# SCH_DTNEA-PRESS-MONITOR-RECIEVER_2021-12.net
KiCad netlist of a schematic drawn in EasyEDA
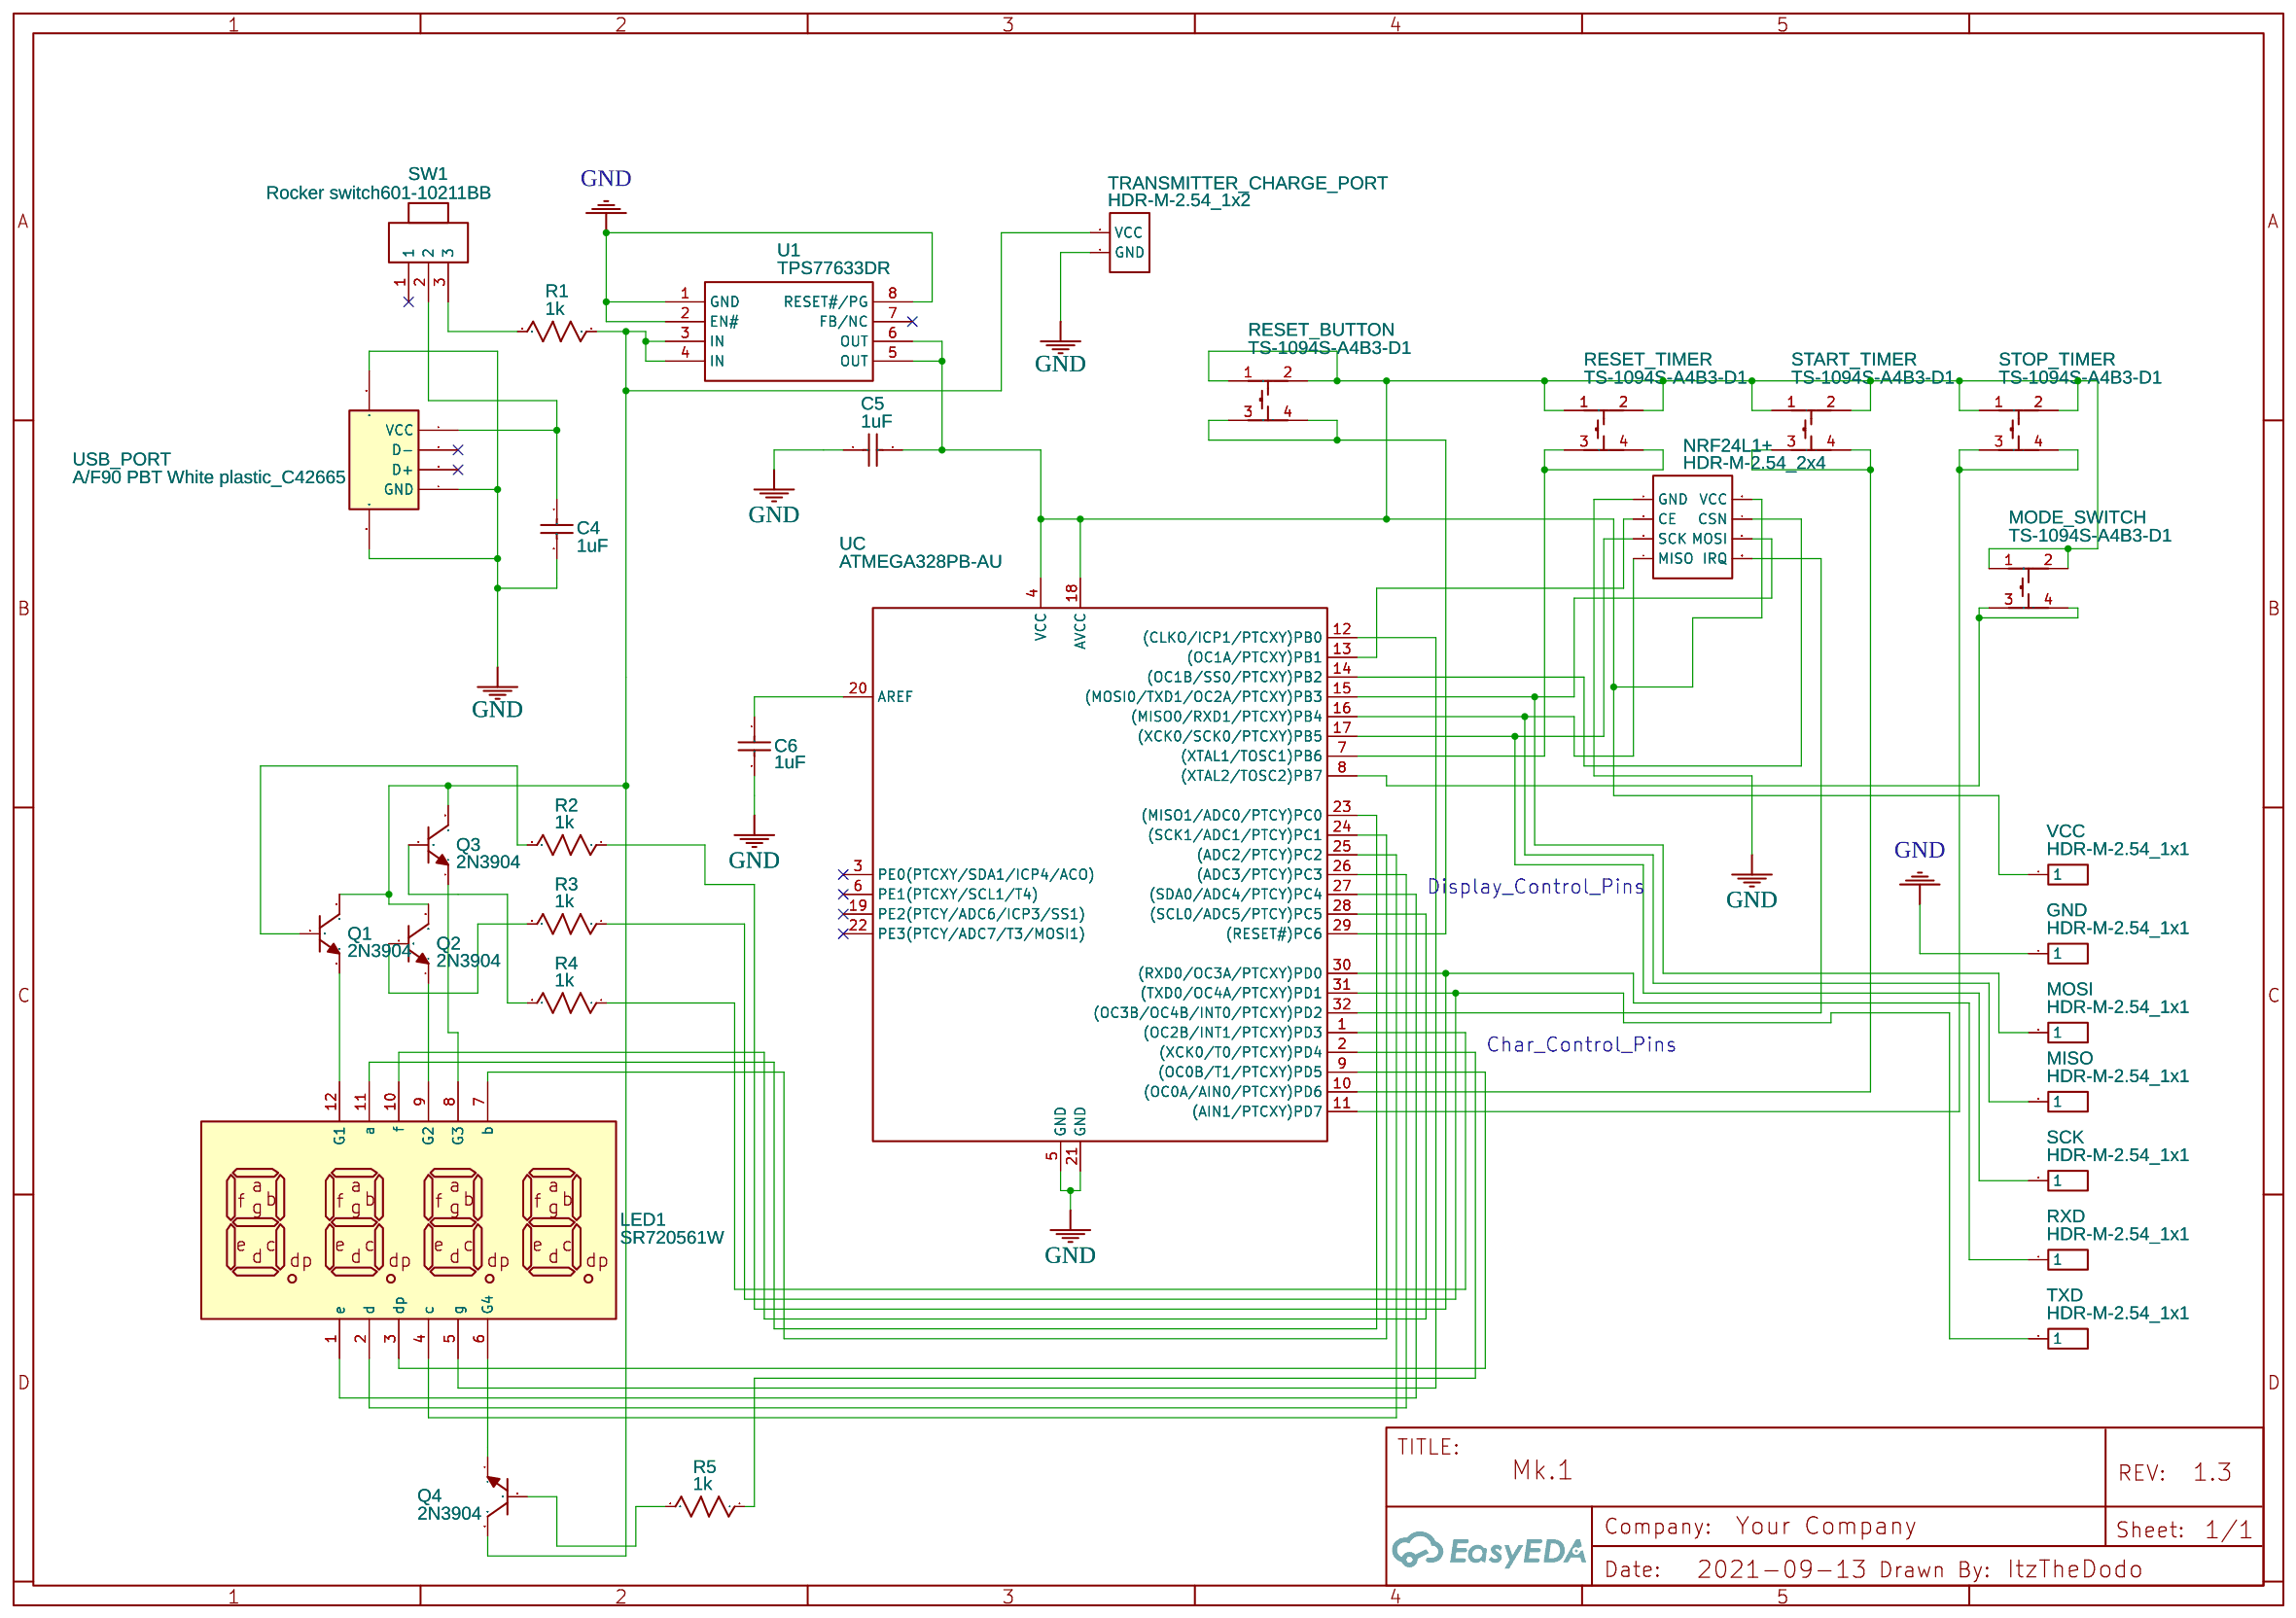
[diagram p0: schematic sheet]

(export (version "E")
  (design (tool "Eeschema 10.0.6"))
  (components
    (comp (ref "C4")
      (value "1uF")
      (fields
        (field (name "BOM_Manufacturer Part") "0603F105M250NT")
        (field (name "BOM_Supplier Part") "C36577")
      )
      (libsource (lib "") (part "0603F105M250NT"))
    )
    (comp (ref "C5")
      (value "1uF")
      (fields
        (field (name "BOM_Manufacturer Part") "0603F105M250NT")
        (field (name "BOM_Supplier Part") "C36577")
      )
      (libsource (lib "") (part "0603F105M250NT_1"))
    )
    (comp (ref "C6")
      (value "1uF")
      (fields
        (field (name "BOM_Manufacturer Part") "0603F105M250NT")
        (field (name "BOM_Supplier Part") "C36577")
      )
      (libsource (lib "") (part "0603F105M250NT"))
    )
    (comp (ref "GND")
      (value "HDR-M-2.54_1x1")
      (fields (field (name "BOM_Supplier Part") "C81276"))
      (libsource (lib "") (part "HDR-M-2.54_1x1_4"))
    )
    (comp (ref "LED1")
      (value "SR720561W")
      (fields (field (name "BOM_Supplier Part") "C111085"))
      (libsource (lib "") (part "SR720561W"))
    )
    (comp (ref "MISO")
      (value "HDR-M-2.54_1x1")
      (fields (field (name "BOM_Supplier Part") "C81276"))
      (libsource (lib "") (part "HDR-M-2.54_1x1"))
    )
    (comp (ref "MODE_SWITCH")
      (value "TS-1094S-A4B3-D1")
      (fields (field (name "BOM_Supplier Part") "C492972"))
      (libsource (lib "") (part "TS-1094S-A4B3-D1_1"))
    )
    (comp (ref "MOSI")
      (value "HDR-M-2.54_1x1")
      (fields (field (name "BOM_Supplier Part") "C81276"))
      (libsource (lib "") (part "HDR-M-2.54_1x1_2"))
    )
    (comp (ref "NRF24L1+")
      (value "HDR-M-2.54_2x4")
      (fields (field (name "BOM_Supplier Part") "C58363"))
      (libsource (lib "") (part "HDR-M-2.54_2x4"))
    )
    (comp (ref "Q1")
      (value "2N3904")
      (fields (field (name "BOM_Supplier Part") "C118538"))
      (libsource (lib "") (part "2N3904"))
    )
    (comp (ref "Q2")
      (value "2N3904")
      (fields (field (name "BOM_Supplier Part") "C118538"))
      (libsource (lib "") (part "2N3904"))
    )
    (comp (ref "Q3")
      (value "2N3904")
      (fields (field (name "BOM_Supplier Part") "C118538"))
      (libsource (lib "") (part "2N3904"))
    )
    (comp (ref "Q4")
      (value "2N3904")
      (fields (field (name "BOM_Supplier Part") "C118538"))
      (libsource (lib "") (part "2N3904_1"))
    )
    (comp (ref "R1") (value "1k") (libsource (lib "") (part "R_0603_US")))
    (comp (ref "R2") (value "1k") (libsource (lib "") (part "R_0603_US")))
    (comp (ref "R3") (value "1k") (libsource (lib "") (part "R_0603_US")))
    (comp (ref "R4") (value "1k") (libsource (lib "") (part "R_0603_US")))
    (comp (ref "R5") (value "1k") (libsource (lib "") (part "R_0603_US")))
    (comp (ref "RESET_BUTTON")
      (value "TS-1094S-A4B3-D1")
      (fields (field (name "BOM_Supplier Part") "C492972"))
      (libsource (lib "") (part "TS-1094S-A4B3-D1"))
    )
    (comp (ref "RESET_TIMER")
      (value "TS-1094S-A4B3-D1")
      (fields (field (name "BOM_Supplier Part") "C492972"))
      (libsource (lib "") (part "TS-1094S-A4B3-D1_2"))
    )
    (comp (ref "RXD")
      (value "HDR-M-2.54_1x1")
      (fields (field (name "BOM_Supplier Part") "C81276"))
      (libsource (lib "") (part "HDR-M-2.54_1x1_6"))
    )
    (comp (ref "SCK")
      (value "HDR-M-2.54_1x1")
      (fields (field (name "BOM_Supplier Part") "C81276"))
      (libsource (lib "") (part "HDR-M-2.54_1x1_5"))
    )
    (comp (ref "START_TIMER")
      (value "TS-1094S-A4B3-D1")
      (fields (field (name "BOM_Supplier Part") "C492972"))
      (libsource (lib "") (part "TS-1094S-A4B3-D1_3"))
    )
    (comp (ref "STOP_TIMER")
      (value "TS-1094S-A4B3-D1")
      (fields (field (name "BOM_Supplier Part") "C492972"))
      (libsource (lib "") (part "TS-1094S-A4B3-D1_4"))
    )
    (comp (ref "SW1")
      (value "Rocker switch601-10211BB")
      (fields (field (name "BOM_Supplier Part") "C67849"))
      (libsource (lib "") (part "Rocker switch601-10211BB"))
    )
    (comp (ref "TRANSMITTER_CHARGE_PORT")
      (value "HDR-M-2.54_1x2")
      (fields (field (name "BOM_Supplier Part") "C124375"))
      (libsource (lib "") (part "HDR-M-2.54_1x2"))
    )
    (comp (ref "TXD")
      (value "HDR-M-2.54_1x1")
      (fields (field (name "BOM_Supplier Part") "C81276"))
      (libsource (lib "") (part "HDR-M-2.54_1x1_3"))
    )
    (comp (ref "U1")
      (value "TPS77633DR")
      (fields (field (name "BOM_Supplier Part") "C130078"))
      (libsource (lib "") (part "TPS77633DR"))
    )
    (comp (ref "UC")
      (value "ATMEGA328PB-AU")
      (fields (field (name "BOM_Supplier Part") "C132230"))
      (libsource (lib "") (part "ATMEGA328PB-AU"))
    )
    (comp (ref "USB_PORT")
      (value "A/F90 PBT White plastic_C42665")
      (fields
        (field (name "BOM_Manufacturer Part") "A/F90 PBT White plastic")
        (field (name "BOM_Supplier Part") "C42665")
      )
      (libsource (lib "") (part "A/F90 PBT White plastic_C42665"))
    )
    (comp (ref "VCC")
      (value "HDR-M-2.54_1x1")
      (fields (field (name "BOM_Supplier Part") "C81276"))
      (libsource (lib "") (part "HDR-M-2.54_1x1_1"))
    )
  )
  (nets
    (net (code "1") (name "GND") (class "Default")
      (node (ref "C4") (pin "2") (pinfunction "2_2") (pintype "input"))
      (node (ref "C5") (pin "2") (pinfunction "2_2") (pintype "input"))
      (node (ref "C6") (pin "2") (pinfunction "2_2") (pintype "input"))
      (node (ref "GND") (pin "1") (pinfunction "1_1") (pintype "input"))
      (node (ref "NRF24L1+") (pin "1") (pinfunction "GND_1") (pintype "unspecified"))
      (node (ref "TRANSMITTER_CHARGE_PORT") (pin "2") (pinfunction "GND_2") (pintype "unspecified"))
      (node (ref "U1") (pin "1") (pinfunction "GND_1") (pintype "passive"))
      (node (ref "U1") (pin "2") (pinfunction "EN#_2") (pintype "unspecified"))
      (node (ref "U1") (pin "8") (pinfunction "RESET#/PG_8") (pintype "unspecified"))
      (node (ref "UC") (pin "21") (pinfunction "GND_21") (pintype "bidirectional"))
      (node (ref "UC") (pin "5") (pinfunction "GND_5") (pintype "bidirectional"))
      (node (ref "USB_PORT") (pin "4") (pinfunction "GND_4") (pintype "input"))
      (node (ref "USB_PORT") (pin "5") (pinfunction "5_5") (pintype "unspecified"))
      (node (ref "USB_PORT") (pin "6") (pinfunction "6_6") (pintype "unspecified"))
    )
    (net (code "2") (name "Net-(LED1-G1)") (class "Default")
      (node (ref "LED1") (pin "12") (pinfunction "G1_12") (pintype "input"))
      (node (ref "Q1") (pin "1") (pinfunction "E_1") (pintype "unspecified"))
    )
    (net (code "3") (name "Net-(LED1-G2)") (class "Default")
      (node (ref "LED1") (pin "9") (pinfunction "G2_9") (pintype "input"))
      (node (ref "Q2") (pin "1") (pinfunction "E_1") (pintype "unspecified"))
    )
    (net (code "4") (name "Net-(LED1-G3)") (class "Default")
      (node (ref "LED1") (pin "8") (pinfunction "G3_8") (pintype "input"))
      (node (ref "Q3") (pin "1") (pinfunction "E_1") (pintype "unspecified"))
    )
    (net (code "5") (name "Net-(LED1-G4)") (class "Default")
      (node (ref "LED1") (pin "6") (pinfunction "G4_6") (pintype "input"))
      (node (ref "Q4") (pin "1") (pinfunction "E_1") (pintype "unspecified"))
    )
    (net (code "6") (name "Net-(LED1-a)") (class "Default")
      (node (ref "LED1") (pin "11") (pinfunction "a_11") (pintype "input"))
      (node (ref "UC") (pin "23") (pinfunction "(MISO1/ADC0/PTCY)PC0_23") (pintype "bidirectional"))
    )
    (net (code "7") (name "Net-(LED1-b)") (class "Default")
      (node (ref "LED1") (pin "7") (pinfunction "b_7") (pintype "input"))
      (node (ref "UC") (pin "24") (pinfunction "(SCK1/ADC1/PTCY)PC1_24") (pintype "bidirectional"))
    )
    (net (code "8") (name "Net-(LED1-c)") (class "Default")
      (node (ref "LED1") (pin "4") (pinfunction "c_4") (pintype "input"))
      (node (ref "UC") (pin "25") (pinfunction "(ADC2/PTCY)PC2_25") (pintype "bidirectional"))
    )
    (net (code "9") (name "Net-(LED1-d)") (class "Default")
      (node (ref "LED1") (pin "2") (pinfunction "d_2") (pintype "input"))
      (node (ref "UC") (pin "26") (pinfunction "(ADC3/PTCY)PC3_26") (pintype "bidirectional"))
    )
    (net (code "10") (name "Net-(LED1-dp)") (class "Default")
      (node (ref "LED1") (pin "3") (pinfunction "dp_3") (pintype "input"))
      (node (ref "UC") (pin "9") (pinfunction "(OC0B/T1/PTCXY)PD5_9") (pintype "bidirectional"))
    )
    (net (code "11") (name "Net-(LED1-e)") (class "Default")
      (node (ref "LED1") (pin "1") (pinfunction "e_1") (pintype "input"))
      (node (ref "UC") (pin "27") (pinfunction "(SDA0/ADC4/PTCY)PC4_27") (pintype "bidirectional"))
    )
    (net (code "12") (name "Net-(LED1-f)") (class "Default")
      (node (ref "LED1") (pin "10") (pinfunction "f_10") (pintype "input"))
      (node (ref "UC") (pin "28") (pinfunction "(SCL0/ADC5/PTCY)PC5_28") (pintype "bidirectional"))
    )
    (net (code "13") (name "Net-(LED1-g)") (class "Default")
      (node (ref "LED1") (pin "5") (pinfunction "g_5") (pintype "input"))
      (node (ref "UC") (pin "12") (pinfunction "(CLKO/ICP1/PTCXY)PB0_12") (pintype "bidirectional"))
    )
    (net (code "14") (name "Net-(NRF24L1+-CE)") (class "Default")
      (node (ref "NRF24L1+") (pin "3") (pinfunction "CE_3") (pintype "unspecified"))
      (node (ref "UC") (pin "13") (pinfunction "(OC1A/PTCXY)PB1_13") (pintype "bidirectional"))
    )
    (net (code "15") (name "Net-(NRF24L1+-CSN)") (class "Default")
      (node (ref "NRF24L1+") (pin "4") (pinfunction "CSN_4") (pintype "unspecified"))
      (node (ref "UC") (pin "14") (pinfunction "(OC1B/SS0/PTCXY)PB2_14") (pintype "bidirectional"))
    )
    (net (code "16") (name "Net-(NRF24L1+-IRQ)") (class "Default")
      (node (ref "NRF24L1+") (pin "8") (pinfunction "IRQ_8") (pintype "unspecified"))
      (node (ref "UC") (pin "32") (pinfunction "(OC3B/OC4B/INT0/PTCXY)PD2_32") (pintype "bidirectional"))
    )
    (net (code "17") (name "Net-(NRF24L1+-MISO)") (class "Default")
      (node (ref "MISO") (pin "1") (pinfunction "1_1") (pintype "input"))
      (node (ref "NRF24L1+") (pin "7") (pinfunction "MISO_7") (pintype "unspecified"))
      (node (ref "UC") (pin "16") (pinfunction "(MISO0/RXD1/PTCXY)PB4_16") (pintype "bidirectional"))
    )
    (net (code "18") (name "Net-(NRF24L1+-MOSI)") (class "Default")
      (node (ref "MOSI") (pin "1") (pinfunction "1_1") (pintype "input"))
      (node (ref "NRF24L1+") (pin "6") (pinfunction "MOSI_6") (pintype "unspecified"))
      (node (ref "UC") (pin "15") (pinfunction "(MOSI0/TXD1/OC2A/PTCXY)PB3_15") (pintype "bidirectional"))
    )
    (net (code "19") (name "Net-(NRF24L1+-SCK)") (class "Default")
      (node (ref "NRF24L1+") (pin "5") (pinfunction "SCK_5") (pintype "unspecified"))
      (node (ref "SCK") (pin "1") (pinfunction "1_1") (pintype "input"))
      (node (ref "UC") (pin "17") (pinfunction "(XCK0/SCK0/PTCXY)PB5_17") (pintype "bidirectional"))
    )
    (net (code "20") (name "Net-(NRF24L1+-VCC)") (class "Default")
      (node (ref "C5") (pin "1") (pinfunction "1_1") (pintype "input"))
      (node (ref "MODE_SWITCH") (pin "1") (pinfunction "1_1") (pintype "unspecified"))
      (node (ref "MODE_SWITCH") (pin "2") (pinfunction "2_2") (pintype "unspecified"))
      (node (ref "NRF24L1+") (pin "2") (pinfunction "VCC_2") (pintype "unspecified"))
      (node (ref "RESET_BUTTON") (pin "1") (pinfunction "1_1") (pintype "unspecified"))
      (node (ref "RESET_BUTTON") (pin "2") (pinfunction "2_2") (pintype "unspecified"))
      (node (ref "RESET_TIMER") (pin "1") (pinfunction "1_1") (pintype "unspecified"))
      (node (ref "RESET_TIMER") (pin "2") (pinfunction "2_2") (pintype "unspecified"))
      (node (ref "START_TIMER") (pin "1") (pinfunction "1_1") (pintype "unspecified"))
      (node (ref "START_TIMER") (pin "2") (pinfunction "2_2") (pintype "unspecified"))
      (node (ref "STOP_TIMER") (pin "1") (pinfunction "1_1") (pintype "unspecified"))
      (node (ref "STOP_TIMER") (pin "2") (pinfunction "2_2") (pintype "unspecified"))
      (node (ref "U1") (pin "5") (pinfunction "OUT_5") (pintype "passive"))
      (node (ref "U1") (pin "6") (pinfunction "OUT_6") (pintype "passive"))
      (node (ref "UC") (pin "18") (pinfunction "AVCC_18") (pintype "bidirectional"))
      (node (ref "UC") (pin "4") (pinfunction "VCC_4") (pintype "bidirectional"))
      (node (ref "VCC") (pin "1") (pinfunction "1_1") (pintype "input"))
    )
    (net (code "21") (name "Net-(Q1-B)") (class "Default")
      (node (ref "Q1") (pin "2") (pinfunction "B_2") (pintype "unspecified"))
      (node (ref "R2") (pin "2") (pinfunction "2_2") (pintype "unspecified"))
    )
    (net (code "22") (name "Net-(Q1-C)") (class "Default")
      (node (ref "Q1") (pin "3") (pinfunction "C_3") (pintype "unspecified"))
      (node (ref "Q2") (pin "3") (pinfunction "C_3") (pintype "unspecified"))
      (node (ref "Q3") (pin "3") (pinfunction "C_3") (pintype "unspecified"))
      (node (ref "Q4") (pin "3") (pinfunction "C_3") (pintype "unspecified"))
      (node (ref "R1") (pin "1") (pinfunction "1_1") (pintype "unspecified"))
      (node (ref "TRANSMITTER_CHARGE_PORT") (pin "1") (pinfunction "VCC_1") (pintype "unspecified"))
      (node (ref "U1") (pin "3") (pinfunction "IN_3") (pintype "passive"))
      (node (ref "U1") (pin "4") (pinfunction "IN_4") (pintype "passive"))
    )
    (net (code "23") (name "Net-(Q2-B)") (class "Default")
      (node (ref "Q2") (pin "2") (pinfunction "B_2") (pintype "unspecified"))
      (node (ref "R3") (pin "2") (pinfunction "2_2") (pintype "unspecified"))
    )
    (net (code "24") (name "Net-(Q3-B)") (class "Default")
      (node (ref "Q3") (pin "2") (pinfunction "B_2") (pintype "unspecified"))
      (node (ref "R4") (pin "2") (pinfunction "2_2") (pintype "unspecified"))
    )
    (net (code "25") (name "Net-(Q4-B)") (class "Default")
      (node (ref "Q4") (pin "2") (pinfunction "B_2") (pintype "unspecified"))
      (node (ref "R5") (pin "2") (pinfunction "2_2") (pintype "unspecified"))
    )
    (net (code "26") (name "Net-(R1-Pad2)") (class "Default")
      (node (ref "R1") (pin "2") (pinfunction "2_2") (pintype "unspecified"))
      (node (ref "SW1") (pin "3") (pinfunction "3_3") (pintype "unspecified"))
    )
    (net (code "27") (name "Net-(UC-(AIN1{slash}PTCXY)PD7)") (class "Default")
      (node (ref "STOP_TIMER") (pin "3") (pinfunction "3_3") (pintype "unspecified"))
      (node (ref "STOP_TIMER") (pin "4") (pinfunction "4_4") (pintype "unspecified"))
      (node (ref "UC") (pin "11") (pinfunction "(AIN1/PTCXY)PD7_11") (pintype "bidirectional"))
    )
    (net (code "28") (name "Net-(UC-(OC0A{slash}AIN0{slash}PTCXY)PD6)") (class "Default")
      (node (ref "START_TIMER") (pin "3") (pinfunction "3_3") (pintype "unspecified"))
      (node (ref "START_TIMER") (pin "4") (pinfunction "4_4") (pintype "unspecified"))
      (node (ref "UC") (pin "10") (pinfunction "(OC0A/AIN0/PTCXY)PD6_10") (pintype "bidirectional"))
    )
    (net (code "29") (name "Net-(UC-(OC2B{slash}INT1{slash}PTCXY)PD3)") (class "Default")
      (node (ref "R4") (pin "1") (pinfunction "1_1") (pintype "unspecified"))
      (node (ref "UC") (pin "1") (pinfunction "(OC2B/INT1/PTCXY)PD3_1") (pintype "bidirectional"))
    )
    (net (code "30") (name "Net-(UC-(RESET#)PC6)") (class "Default")
      (node (ref "RESET_BUTTON") (pin "3") (pinfunction "3_3") (pintype "unspecified"))
      (node (ref "RESET_BUTTON") (pin "4") (pinfunction "4_4") (pintype "unspecified"))
      (node (ref "UC") (pin "29") (pinfunction "(RESET#)PC6_29") (pintype "bidirectional"))
    )
    (net (code "31") (name "Net-(UC-(RXD0{slash}OC3A{slash}PTCXY)PD0)") (class "Default")
      (node (ref "R2") (pin "1") (pinfunction "1_1") (pintype "unspecified"))
      (node (ref "RXD") (pin "1") (pinfunction "1_1") (pintype "input"))
      (node (ref "UC") (pin "30") (pinfunction "(RXD0/OC3A/PTCXY)PD0_30") (pintype "bidirectional"))
    )
    (net (code "32") (name "Net-(UC-(TXD0{slash}OC4A{slash}PTCXY)PD1)") (class "Default")
      (node (ref "R3") (pin "1") (pinfunction "1_1") (pintype "unspecified"))
      (node (ref "TXD") (pin "1") (pinfunction "1_1") (pintype "input"))
      (node (ref "UC") (pin "31") (pinfunction "(TXD0/OC4A/PTCXY)PD1_31") (pintype "bidirectional"))
    )
    (net (code "33") (name "Net-(UC-(XCK0{slash}T0{slash}PTCXY)PD4)") (class "Default")
      (node (ref "R5") (pin "1") (pinfunction "1_1") (pintype "unspecified"))
      (node (ref "UC") (pin "2") (pinfunction "(XCK0/T0/PTCXY)PD4_2") (pintype "bidirectional"))
    )
    (net (code "34") (name "Net-(UC-(XTAL1{slash}TOSC1)PB6)") (class "Default")
      (node (ref "RESET_TIMER") (pin "3") (pinfunction "3_3") (pintype "unspecified"))
      (node (ref "RESET_TIMER") (pin "4") (pinfunction "4_4") (pintype "unspecified"))
      (node (ref "UC") (pin "7") (pinfunction "(XTAL1/TOSC1)PB6_7") (pintype "bidirectional"))
    )
    (net (code "35") (name "Net-(UC-(XTAL2{slash}TOSC2)PB7)") (class "Default")
      (node (ref "MODE_SWITCH") (pin "3") (pinfunction "3_3") (pintype "unspecified"))
      (node (ref "MODE_SWITCH") (pin "4") (pinfunction "4_4") (pintype "unspecified"))
      (node (ref "UC") (pin "8") (pinfunction "(XTAL2/TOSC2)PB7_8") (pintype "bidirectional"))
    )
    (net (code "36") (name "Net-(UC-AREF)") (class "Default")
      (node (ref "C6") (pin "1") (pinfunction "1_1") (pintype "input"))
      (node (ref "UC") (pin "20") (pinfunction "AREF_20") (pintype "bidirectional"))
    )
    (net (code "37") (name "Net-(USB_PORT-VCC)") (class "Default")
      (node (ref "C4") (pin "1") (pinfunction "1_1") (pintype "input"))
      (node (ref "SW1") (pin "2") (pinfunction "2_2") (pintype "unspecified"))
      (node (ref "USB_PORT") (pin "1") (pinfunction "VCC_1") (pintype "input"))
    )
    (net (code "38") (name "unconnected-(SW1-Pad1)") (class "Default")
      (node (ref "SW1") (pin "1") (pinfunction "1_1") (pintype "unspecified+no_connect"))
    )
    (net (code "39") (name "unconnected-(U1-FB{slash}NC-Pad7)") (class "Default")
      (node (ref "U1") (pin "7") (pinfunction "FB/NC_7") (pintype "unspecified+no_connect"))
    )
    (net (code "40") (name "unconnected-(UC-PE0(PTCXY{slash}SDA1{slash}ICP4{slash}ACO)-Pad3)") (class "Default")
      (node (ref "UC") (pin "3") (pinfunction "PE0(PTCXY/SDA1/ICP4/ACO)_3") (pintype "bidirectional+no_connect"))
    )
    (net (code "41") (name "unconnected-(UC-PE1(PTCXY{slash}SCL1{slash}T4)-Pad6)") (class "Default")
      (node (ref "UC") (pin "6") (pinfunction "PE1(PTCXY/SCL1/T4)_6") (pintype "bidirectional+no_connect"))
    )
    (net (code "42") (name "unconnected-(UC-PE2(PTCY{slash}ADC6{slash}ICP3{slash}SS1)-Pad19)") (class "Default")
      (node (ref "UC") (pin "19") (pinfunction "PE2(PTCY/ADC6/ICP3/SS1)_19") (pintype "bidirectional+no_connect"))
    )
    (net (code "43") (name "unconnected-(UC-PE3(PTCY{slash}ADC7{slash}T3{slash}MOSI1)-Pad22)") (class "Default")
      (node (ref "UC") (pin "22") (pinfunction "PE3(PTCY/ADC7/T3/MOSI1)_22") (pintype "bidirectional+no_connect"))
    )
    (net (code "44") (name "unconnected-(USB_PORT-D+-Pad3)") (class "Default")
      (node (ref "USB_PORT") (pin "3") (pinfunction "D+_3") (pintype "input+no_connect"))
    )
    (net (code "45") (name "unconnected-(USB_PORT-D--Pad2)") (class "Default")
      (node (ref "USB_PORT") (pin "2") (pinfunction "D-_2") (pintype "input+no_connect"))
    )
  )
)
